# BalanceCar.net
KiCad netlist of a schematic drawn in Altium Designer
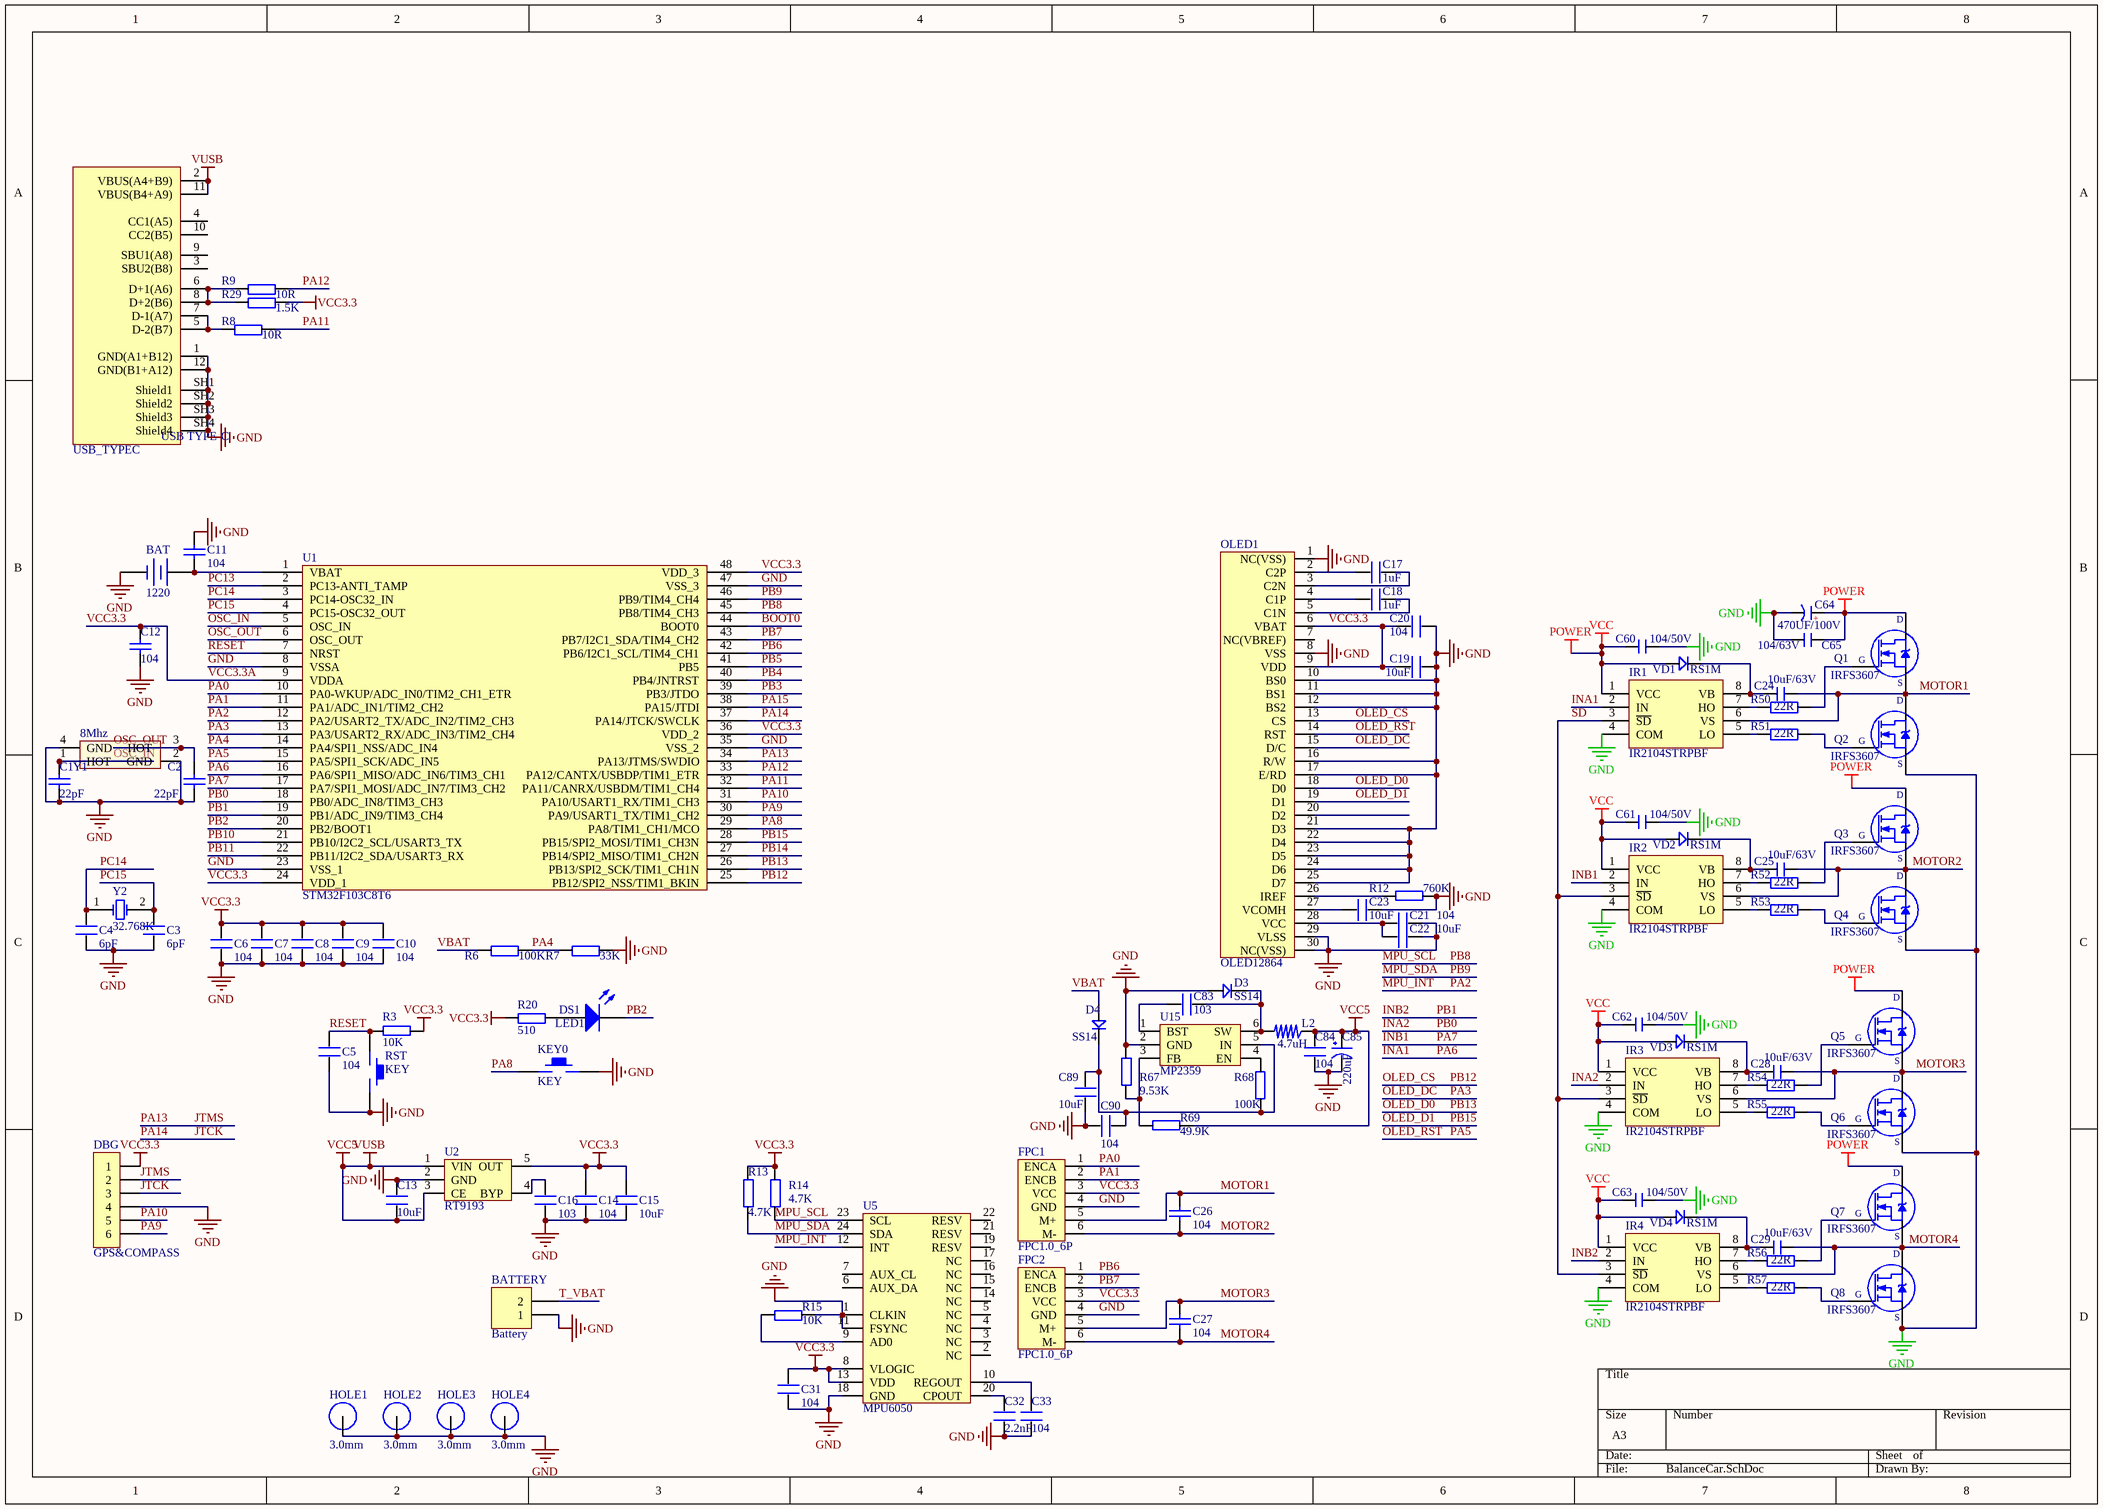
[diagram p0: BalanceCar.SchDoc]

(export (version "E")
  (design (tool "Eeschema 10.0.6"))
  (components
    (comp (ref "BAT")
      (value "1220")
      (footprint "CR1220_B")
      (description "微型电池")
      (fields (field (name "版权归属") "源创客"))
      (libsource (lib "IMX6UL_ALPHA(底板)_V2.0") (part "CR-3V"))
    )
    (comp (ref "BATTERY")
      (value "Battery")
      (footprint "HDR2.54-LI-2P")
      (description "Header, 2-Pin")
      (fields (field (name "PUBLISHER") "Altium Limited"))
      (libsource (lib "WarShip V3 STM32103封装库") (part "Header 2"))
    )
    (comp (ref "C1") (value "22pF") (footprint "C 0603_L") (libsource (lib "L476") (part "CAP")))
    (comp (ref "C2") (value "22pF") (footprint "C 0603_L") (libsource (lib "L476") (part "CAP")))
    (comp (ref "C3")
      (value "6pF")
      (footprint "C 0603_L")
      (libsource (lib "WarShip V3 STM32103封装库") (part "C"))
    )
    (comp (ref "C4")
      (value "6pF")
      (footprint "C 0603_L")
      (libsource (lib "WarShip V3 STM32103封装库") (part "C"))
    )
    (comp (ref "C5")
      (value "104")
      (footprint "C 0603_L")
      (libsource (lib "WarShip V3 STM32103封装库") (part "C"))
    )
    (comp (ref "C6")
      (value "104")
      (footprint "C 0603_L")
      (libsource (lib "WarShip V3 STM32103封装库") (part "C"))
    )
    (comp (ref "C7")
      (value "104")
      (footprint "C 0603_L")
      (libsource (lib "WarShip V3 STM32103封装库") (part "C"))
    )
    (comp (ref "C8")
      (value "104")
      (footprint "C 0603_L")
      (libsource (lib "WarShip V3 STM32103封装库") (part "C"))
    )
    (comp (ref "C9")
      (value "104")
      (footprint "C 0603_L")
      (libsource (lib "WarShip V3 STM32103封装库") (part "C"))
    )
    (comp (ref "C10")
      (value "104")
      (footprint "C 0603_L")
      (libsource (lib "WarShip V3 STM32103封装库") (part "C"))
    )
    (comp (ref "C11") (value "104") (footprint "C 0603_L") (libsource (lib "L476") (part "CAP")))
    (comp (ref "C12") (value "104") (footprint "C 0603_L") (libsource (lib "L476") (part "CAP")))
    (comp (ref "C13")
      (value "10uF")
      (footprint "C 0603_L")
      (libsource (lib "WarShip V3 STM32103封装库") (part "C"))
    )
    (comp (ref "C14")
      (value "104")
      (footprint "C 0603_L")
      (libsource (lib "WarShip V3 STM32103封装库") (part "C"))
    )
    (comp (ref "C15")
      (value "10uF")
      (footprint "C 0603_L")
      (libsource (lib "WarShip V3 STM32103封装库") (part "C"))
    )
    (comp (ref "C16")
      (value "103")
      (footprint "C 0603_L")
      (libsource (lib "WarShip V3 STM32103封装库") (part "C"))
    )
    (comp (ref "C17")
      (value "1uF")
      (footprint "C 0603_L")
      (libsource (lib "WarShip V3 STM32103封装库") (part "C"))
    )
    (comp (ref "C18")
      (value "1uF")
      (footprint "C 0603_L")
      (libsource (lib "WarShip V3 STM32103封装库") (part "C"))
    )
    (comp (ref "C19")
      (value "10uF")
      (footprint "C 0603_L")
      (libsource (lib "WarShip V3 STM32103封装库") (part "C"))
    )
    (comp (ref "C20")
      (value "104")
      (footprint "C 0603_L")
      (libsource (lib "WarShip V3 STM32103封装库") (part "C"))
    )
    (comp (ref "C21")
      (value "10uF")
      (footprint "C 0603_L")
      (libsource (lib "WarShip V3 STM32103封装库") (part "C"))
    )
    (comp (ref "C22")
      (value "104")
      (footprint "C 0603_L")
      (libsource (lib "WarShip V3 STM32103封装库") (part "C"))
    )
    (comp (ref "C23")
      (value "10uF")
      (footprint "C 0603_L")
      (libsource (lib "WarShip V3 STM32103封装库") (part "C"))
    )
    (comp (ref "C24")
      (value "10uF/63V")
      (footprint "C 0603_L")
      (description "无极性贴片电容")
      (fields (field (name "版权归属") "源创客"))
      (libsource (lib "电阻-电容-电感") (part "C"))
    )
    (comp (ref "C25")
      (value "10uF/63V")
      (footprint "C 0603_L")
      (description "无极性贴片电容")
      (fields (field (name "版权归属") "源创客"))
      (libsource (lib "电阻-电容-电感") (part "C"))
    )
    (comp (ref "C26") (value "104") (footprint "C 0603_L") (libsource (lib "L476") (part "CAP")))
    (comp (ref "C27") (value "104") (footprint "C 0603_L") (libsource (lib "L476") (part "CAP")))
    (comp (ref "C28")
      (value "10uF/63V")
      (footprint "C 0603_L")
      (description "无极性贴片电容")
      (fields (field (name "版权归属") "源创客"))
      (libsource (lib "电阻-电容-电感") (part "C"))
    )
    (comp (ref "C29")
      (value "10uF/63V")
      (footprint "C 0603_L")
      (description "无极性贴片电容")
      (fields (field (name "版权归属") "源创客"))
      (libsource (lib "电阻-电容-电感") (part "C"))
    )
    (comp (ref "C31")
      (value "104")
      (footprint "C 0603_L")
      (libsource (lib "WarShip V3 STM32103封装库") (part "C"))
    )
    (comp (ref "C32")
      (value "2.2nF")
      (footprint "C 0603_L")
      (libsource (lib "WarShip V3 STM32103封装库") (part "C"))
    )
    (comp (ref "C33")
      (value "104")
      (footprint "C 0603_L")
      (libsource (lib "WarShip V3 STM32103封装库") (part "C"))
    )
    (comp (ref "C60")
      (value "104/50V")
      (footprint "C 0603_L")
      (description "无极性贴片电容")
      (fields (field (name "版权归属") "源创客"))
      (libsource (lib "电阻-电容-电感") (part "C"))
    )
    (comp (ref "C61")
      (value "104/50V")
      (footprint "C 0603_L")
      (description "无极性贴片电容")
      (fields (field (name "版权归属") "源创客"))
      (libsource (lib "电阻-电容-电感") (part "C"))
    )
    (comp (ref "C62")
      (value "104/50V")
      (footprint "C 0603_L")
      (description "无极性贴片电容")
      (fields (field (name "版权归属") "源创客"))
      (libsource (lib "电阻-电容-电感") (part "C"))
    )
    (comp (ref "C63")
      (value "104/50V")
      (footprint "C 0603_L")
      (description "无极性贴片电容")
      (fields (field (name "版权归属") "源创客"))
      (libsource (lib "电阻-电容-电感") (part "C"))
    )
    (comp (ref "C64")
      (value "470UF/100V")
      (footprint "CAP 5.0*10*20 - BK")
      (description "直插电解电容")
      (fields (field (name "版权归属") "源创客"))
      (libsource (lib "电阻-电容-电感") (part "C-CAP"))
    )
    (comp (ref "C65")
      (value "104/63V")
      (footprint "C 1206_L")
      (description "无极性贴片电容")
      (fields (field (name "版权归属") "源创客"))
      (libsource (lib "电阻-电容-电感") (part "C"))
    )
    (comp (ref "C83") (value "103") (footprint "C 0603_L") (libsource (lib "ALIENTEK_COMPONENT") (part "C")))
    (comp (ref "C84") (value "104") (footprint "C 0603_L") (libsource (lib "MYCOMLIB") (part "C")))
    (comp (ref "C85") (value "220uF") (footprint "CM D(6.3*5.4)") (libsource (lib "MYCOMLIB") (part "CAP")))
    (comp (ref "C89") (value "10uF") (footprint "C 0603_L") (libsource (lib "ALIENTEK_COMPONENT") (part "C")))
    (comp (ref "C90") (value "104") (footprint "C 0603_L") (libsource (lib "MYCOMLIB") (part "C")))
    (comp (ref "D3")
      (value "SS14")
      (footprint "SMA")
      (description "1N4148")
      (libsource (lib "MYCOMLIB") (part "D"))
    )
    (comp (ref "D4")
      (value "SS14")
      (footprint "SMA")
      (description "1N4148")
      (libsource (lib "MYCOMLIB") (part "D"))
    )
    (comp (ref "DBG")
      (value "GPS&COMPASS")
      (footprint "SH1.0 S-W-6P")
      (description "6P接插件")
      (fields (field (name "版权归属") "源创客"))
      (libsource (lib "ATKF405 V1.1") (part "Header 6"))
    )
    (comp (ref "DS1")
      (value "LED1")
      (footprint "LED 0603R")
      (description "Typical RED, GREEN, YELLOW, AMBER GaAs LED")
      (fields (field (name "PUBLISHER") "Altium Limited"))
      (libsource (lib "WarShip V3 STM32103封装库") (part "LED2"))
    )
    (comp (ref "FPC1")
      (value "FPC1.0_6P")
      (footprint "FPC_1.0_6P")
      (libsource (lib "MOTOR_FPC") (part "FPC"))
    )
    (comp (ref "FPC2")
      (value "FPC1.0_6P")
      (footprint "FPC_1.0_6P")
      (libsource (lib "MOTOR_FPC") (part "FPC"))
    )
    (comp (ref "HOLE1")
      (value "3.0mm")
      (footprint "HOLE-M3")
      (fields (field (name "Comment") "HOLE"))
      (libsource (lib "YS_BDC_V1") (part "HOLE"))
    )
    (comp (ref "HOLE2")
      (value "3.0mm")
      (footprint "HOLE-M3")
      (fields (field (name "Comment") "HOLE"))
      (libsource (lib "YS_BDC_V1") (part "HOLE"))
    )
    (comp (ref "HOLE3")
      (value "3.0mm")
      (footprint "HOLE-M3")
      (fields (field (name "Comment") "HOLE"))
      (libsource (lib "YS_BDC_V1") (part "HOLE"))
    )
    (comp (ref "HOLE4")
      (value "3.0mm")
      (footprint "HOLE-M3")
      (fields (field (name "Comment") "HOLE"))
      (libsource (lib "YS_BDC_V1") (part "HOLE"))
    )
    (comp (ref "IR1")
      (value "IR2104STRPBF")
      (footprint "SOP8_L")
      (description "HALF-BRIDGE DRIVER")
      (libsource (lib "YS_BDC_V1") (part "IR2104STRPBF"))
    )
    (comp (ref "IR2")
      (value "IR2104STRPBF")
      (footprint "SOP8_L")
      (description "HALF-BRIDGE DRIVER")
      (libsource (lib "YS_BDC_V1") (part "IR2104STRPBF"))
    )
    (comp (ref "IR3")
      (value "IR2104STRPBF")
      (footprint "SOP8_L")
      (description "HALF-BRIDGE DRIVER")
      (libsource (lib "YS_BDC_V1") (part "IR2104STRPBF"))
    )
    (comp (ref "IR4")
      (value "IR2104STRPBF")
      (footprint "SOP8_L")
      (description "HALF-BRIDGE DRIVER")
      (libsource (lib "YS_BDC_V1") (part "IR2104STRPBF"))
    )
    (comp (ref "KEY0")
      (value "KEY")
      (footprint "TSW DIP-6*6*9")
      (libsource (lib "STM32F429核心板封装库") (part "KEY_M"))
    )
    (comp (ref "L2")
      (value "4.7uH")
      (footprint "CDRH73")
      (libsource (lib "ALIENTEK_COMPONENT") (part "L_SOP"))
    )
    (comp (ref "OLED1") (value "OLED12864") (libsource (lib "OLED模块封装库") (part "OLED12864")))
    (comp (ref "Q1")
      (value "IRFS3607")
      (footprint "TO263-3B")
      (description "N-Channel Power MOSFET")
      (fields (field (name "PUBLISHER") "Altium Limited"))
      (libsource (lib "YS_BDC_V1") (part "NMOS-2"))
    )
    (comp (ref "Q2")
      (value "IRFS3607")
      (footprint "TO263-3B")
      (description "N-Channel Power MOSFET")
      (fields (field (name "PUBLISHER") "Altium Limited"))
      (libsource (lib "YS_BDC_V1") (part "NMOS-2"))
    )
    (comp (ref "Q3")
      (value "IRFS3607")
      (footprint "TO263-3B")
      (description "N-Channel Power MOSFET")
      (fields (field (name "PUBLISHER") "Altium Limited"))
      (libsource (lib "YS_BDC_V1") (part "NMOS-2"))
    )
    (comp (ref "Q4")
      (value "IRFS3607")
      (footprint "TO263-3B")
      (description "N-Channel Power MOSFET")
      (fields (field (name "PUBLISHER") "Altium Limited"))
      (libsource (lib "YS_BDC_V1") (part "NMOS-2"))
    )
    (comp (ref "Q5")
      (value "IRFS3607")
      (footprint "TO263-3B")
      (description "N-Channel Power MOSFET")
      (fields (field (name "PUBLISHER") "Altium Limited"))
      (libsource (lib "YS_BDC_V1") (part "NMOS-2"))
    )
    (comp (ref "Q6")
      (value "IRFS3607")
      (footprint "TO263-3B")
      (description "N-Channel Power MOSFET")
      (fields (field (name "PUBLISHER") "Altium Limited"))
      (libsource (lib "YS_BDC_V1") (part "NMOS-2"))
    )
    (comp (ref "Q7")
      (value "IRFS3607")
      (footprint "TO263-3B")
      (description "N-Channel Power MOSFET")
      (fields (field (name "PUBLISHER") "Altium Limited"))
      (libsource (lib "YS_BDC_V1") (part "NMOS-2"))
    )
    (comp (ref "Q8")
      (value "IRFS3607")
      (footprint "TO263-3B")
      (description "N-Channel Power MOSFET")
      (fields (field (name "PUBLISHER") "Altium Limited"))
      (libsource (lib "YS_BDC_V1") (part "NMOS-2"))
    )
    (comp (ref "R3")
      (value "10K")
      (footprint "R 0603_L")
      (libsource (lib "WarShip V3 STM32103封装库") (part "R"))
    )
    (comp (ref "R6")
      (value "100K")
      (footprint "R 0603_L")
      (libsource (lib "WarShip V3 STM32103封装库") (part "R"))
    )
    (comp (ref "R7")
      (value "33K")
      (footprint "R 0603_L")
      (libsource (lib "WarShip V3 STM32103封装库") (part "R"))
    )
    (comp (ref "R8")
      (value "10R")
      (footprint "R 0603_L")
      (libsource (lib "WarShip V3 STM32103封装库") (part "R"))
    )
    (comp (ref "R9")
      (value "10R")
      (footprint "R 0603_L")
      (libsource (lib "WarShip V3 STM32103封装库") (part "R"))
    )
    (comp (ref "R12")
      (value "760K")
      (footprint "R 0603_L")
      (libsource (lib "WarShip V3 STM32103封装库") (part "R"))
    )
    (comp (ref "R13")
      (value "4.7K")
      (footprint "R 0603_L")
      (libsource (lib "WarShip V3 STM32103封装库") (part "R"))
    )
    (comp (ref "R14")
      (value "4.7K")
      (footprint "R 0603_L")
      (libsource (lib "WarShip V3 STM32103封装库") (part "R"))
    )
    (comp (ref "R15")
      (value "10K")
      (footprint "R 0603_L")
      (libsource (lib "WarShip V3 STM32103封装库") (part "R"))
    )
    (comp (ref "R20")
      (value "510")
      (footprint "R 0603_L")
      (libsource (lib "WarShip V3 STM32103封装库") (part "R"))
    )
    (comp (ref "R29")
      (value "1.5K")
      (footprint "R 0603_L")
      (libsource (lib "WarShip V3 STM32103封装库") (part "R"))
    )
    (comp (ref "R50")
      (value "22R")
      (footprint "R 0603_L")
      (description "贴片电阻")
      (fields (field (name "版权归属") "源创客"))
      (libsource (lib "电阻-电容-电感") (part "R"))
    )
    (comp (ref "R51")
      (value "22R")
      (footprint "R 0603_L")
      (description "贴片电阻")
      (fields (field (name "版权归属") "源创客"))
      (libsource (lib "电阻-电容-电感") (part "R"))
    )
    (comp (ref "R52")
      (value "22R")
      (footprint "R 0603_L")
      (description "贴片电阻")
      (fields (field (name "版权归属") "源创客"))
      (libsource (lib "电阻-电容-电感") (part "R"))
    )
    (comp (ref "R53")
      (value "22R")
      (footprint "R 0603_L")
      (description "贴片电阻")
      (fields (field (name "版权归属") "源创客"))
      (libsource (lib "电阻-电容-电感") (part "R"))
    )
    (comp (ref "R54")
      (value "22R")
      (footprint "R 0603_L")
      (description "贴片电阻")
      (fields (field (name "版权归属") "源创客"))
      (libsource (lib "电阻-电容-电感") (part "R"))
    )
    (comp (ref "R55")
      (value "22R")
      (footprint "R 0603_L")
      (description "贴片电阻")
      (fields (field (name "版权归属") "源创客"))
      (libsource (lib "电阻-电容-电感") (part "R"))
    )
    (comp (ref "R56")
      (value "22R")
      (footprint "R 0603_L")
      (description "贴片电阻")
      (fields (field (name "版权归属") "源创客"))
      (libsource (lib "电阻-电容-电感") (part "R"))
    )
    (comp (ref "R57")
      (value "22R")
      (footprint "R 0603_L")
      (description "贴片电阻")
      (fields (field (name "版权归属") "源创客"))
      (libsource (lib "电阻-电容-电感") (part "R"))
    )
    (comp (ref "R67")
      (value "9.53K")
      (footprint "R 0603_L")
      (libsource (lib "ALIENTEK_COMPONENT") (part "R"))
    )
    (comp (ref "R68") (value "100K") (footprint "R 0603_L") (libsource (lib "ALIENTEK_COMPONENT") (part "R")))
    (comp (ref "R69")
      (value "49.9K")
      (footprint "R 0603_L")
      (libsource (lib "ALIENTEK_COMPONENT") (part "R"))
    )
    (comp (ref "RST") (value "KEY") (footprint "TSW DIP-6*6*9") (libsource (lib "") (part "KEY_M_1")))
    (comp (ref "U1")
      (value "STM32F103C8T6")
      (footprint "LQFP-48PIN")
      (libsource (lib "Pandora_STM32L4_Board_V2.4") (part "U-STM32F103C8T6"))
    )
    (comp (ref "U2")
      (value "RT9193")
      (footprint "SOT23-5L")
      (description "3.3V 500mA LDO")
      (libsource (lib "STM32H743核心板封装库") (part "CAT6219-330TD"))
    )
    (comp (ref "U5")
      (value "MPU6050")
      (footprint "QFN24 4x4_N")
      (description "9轴运动处理传感器")
      (libsource (lib "ATK-MPU6050六轴传感器模块") (part "MPU6050"))
    )
    (comp (ref "U15")
      (value "MP2359")
      (footprint "SOT23-6L")
      (description "DC DC Step Down IC")
      (libsource (lib "ALIENTEK_COMPONENT") (part "MP2359"))
    )
    (comp (ref "USB_TYPEC")
      (value "USB TypeC")
      (footprint "USB Type-C")
      (description "12P TypeC 母座")
      (libsource (lib "ESP32_Weather") (part "USB Type-C"))
    )
    (comp (ref "VD1")
      (value "RS1M")
      (footprint "SOD-123F")
      (description "肖特基二极管")
      (fields (field (name "版权归属") "源创客"))
      (libsource (lib "二极管-整流桥") (part "SS14"))
    )
    (comp (ref "VD2")
      (value "RS1M")
      (footprint "SOD-123F")
      (description "肖特基二极管")
      (fields (field (name "版权归属") "源创客"))
      (libsource (lib "二极管-整流桥") (part "SS14"))
    )
    (comp (ref "VD3")
      (value "RS1M")
      (footprint "SOD-123F")
      (description "肖特基二极管")
      (fields (field (name "版权归属") "源创客"))
      (libsource (lib "二极管-整流桥") (part "SS14"))
    )
    (comp (ref "VD4")
      (value "RS1M")
      (footprint "SOD-123F")
      (description "肖特基二极管")
      (fields (field (name "版权归属") "源创客"))
      (libsource (lib "二极管-整流桥") (part "SS14"))
    )
    (comp (ref "Y1")
      (value "8Mhz")
      (footprint "XTAL-3225")
      (description "3225贴片无源晶振")
      (libsource (lib "ALIENTEK_COMPONENT") (part "XTAL_3225"))
    )
    (comp (ref "Y2")
      (value "32.768K")
      (footprint "OSC 3215-2P")
      (description "Crystal Oscillator")
      (fields (field (name "PUBLISHER") "Altium Limited"))
      (libsource (lib "WarShip V3 STM32103封装库") (part "XTAL"))
    )
  )
  (nets
    (net (code "1") (name "/BOOT0") (class "Default")
      (node (ref "U1") (pin "44") (pinfunction "BOOT0_44") (pintype "passive"))
    )
    (net (code "2") (name "/INA1") (class "Default")
      (node (ref "IR1") (pin "2") (pinfunction "IN_2") (pintype "passive"))
      (node (ref "U1") (pin "16") (pinfunction "PA6/SPI1_MISO/ADC_IN6/TIM3_CH1_16") (pintype "passive"))
    )
    (net (code "3") (name "/INA2") (class "Default")
      (node (ref "IR3") (pin "2") (pinfunction "IN_2") (pintype "passive"))
      (node (ref "U1") (pin "18") (pinfunction "PB0/ADC_IN8/TIM3_CH3_18") (pintype "passive"))
    )
    (net (code "4") (name "/INB1") (class "Default")
      (node (ref "IR2") (pin "2") (pinfunction "IN_2") (pintype "passive"))
      (node (ref "U1") (pin "17") (pinfunction "PA7/SPI1_MOSI/ADC_IN7/TIM3_CH2_17") (pintype "passive"))
    )
    (net (code "5") (name "/INB2") (class "Default")
      (node (ref "IR4") (pin "2") (pinfunction "IN_2") (pintype "passive"))
      (node (ref "U1") (pin "19") (pinfunction "PB1/ADC_IN9/TIM3_CH4_19") (pintype "passive"))
    )
    (net (code "6") (name "/JTCK") (class "Default")
      (node (ref "DBG") (pin "3") (pinfunction "3_3") (pintype "passive"))
      (node (ref "U1") (pin "37") (pinfunction "PA14/JTCK/SWCLK_37") (pintype "passive"))
    )
    (net (code "7") (name "/JTMS") (class "Default")
      (node (ref "DBG") (pin "2") (pinfunction "2_2") (pintype "passive"))
      (node (ref "U1") (pin "34") (pinfunction "PA13/JTMS/SWDIO_34") (pintype "passive"))
    )
    (net (code "8") (name "/MOTOR1") (class "Default")
      (node (ref "C24") (pin "1") (pinfunction "1_1") (pintype "passive"))
      (node (ref "C26") (pin "2") (pinfunction "2_2") (pintype "passive"))
      (node (ref "FPC1") (pin "5") (pinfunction "M+_5") (pintype "passive"))
      (node (ref "IR1") (pin "6") (pinfunction "VS_6") (pintype "passive"))
      (node (ref "Q1") (pin "3") (pinfunction "S_3") (pintype "passive"))
      (node (ref "Q2") (pin "2") (pinfunction "D_2") (pintype "passive"))
    )
    (net (code "9") (name "/MOTOR2") (class "Default")
      (node (ref "C25") (pin "1") (pinfunction "1_1") (pintype "passive"))
      (node (ref "C26") (pin "1") (pinfunction "1_1") (pintype "passive"))
      (node (ref "FPC1") (pin "6") (pinfunction "M-_6") (pintype "passive"))
      (node (ref "IR2") (pin "6") (pinfunction "VS_6") (pintype "passive"))
      (node (ref "Q3") (pin "3") (pinfunction "S_3") (pintype "passive"))
      (node (ref "Q4") (pin "2") (pinfunction "D_2") (pintype "passive"))
    )
    (net (code "10") (name "/MOTOR3") (class "Default")
      (node (ref "C27") (pin "2") (pinfunction "2_2") (pintype "passive"))
      (node (ref "C28") (pin "1") (pinfunction "1_1") (pintype "passive"))
      (node (ref "FPC2") (pin "5") (pinfunction "M+_5") (pintype "passive"))
      (node (ref "IR3") (pin "6") (pinfunction "VS_6") (pintype "passive"))
      (node (ref "Q5") (pin "3") (pinfunction "S_3") (pintype "passive"))
      (node (ref "Q6") (pin "2") (pinfunction "D_2") (pintype "passive"))
    )
    (net (code "11") (name "/MOTOR4") (class "Default")
      (node (ref "C27") (pin "1") (pinfunction "1_1") (pintype "passive"))
      (node (ref "C29") (pin "1") (pinfunction "1_1") (pintype "passive"))
      (node (ref "FPC2") (pin "6") (pinfunction "M-_6") (pintype "passive"))
      (node (ref "IR4") (pin "6") (pinfunction "VS_6") (pintype "passive"))
      (node (ref "Q7") (pin "3") (pinfunction "S_3") (pintype "passive"))
      (node (ref "Q8") (pin "2") (pinfunction "D_2") (pintype "passive"))
    )
    (net (code "12") (name "/MPU_INT") (class "Default")
      (node (ref "U1") (pin "12") (pinfunction "PA2/USART2_TX/ADC_IN2/TIM2_CH3_12") (pintype "passive"))
      (node (ref "U5") (pin "12") (pinfunction "INT_12") (pintype "passive"))
    )
    (net (code "13") (name "/MPU_SCL") (class "Default")
      (node (ref "R14") (pin "1") (pintype "passive"))
      (node (ref "U1") (pin "45") (pinfunction "PB8/TIM4_CH3_45") (pintype "passive"))
      (node (ref "U5") (pin "23") (pinfunction "SCL_23") (pintype "passive"))
    )
    (net (code "14") (name "/MPU_SDA") (class "Default")
      (node (ref "R13") (pin "1") (pintype "passive"))
      (node (ref "U1") (pin "46") (pinfunction "PB9/TIM4_CH4_46") (pintype "passive"))
      (node (ref "U5") (pin "24") (pinfunction "SDA_24") (pintype "passive"))
    )
    (net (code "15") (name "/OLED_CS") (class "Default")
      (node (ref "OLED1") (pin "13") (pinfunction "CS_13") (pintype "passive"))
      (node (ref "U1") (pin "25") (pinfunction "PB12/SPI2_NSS/TIM1_BKIN_25") (pintype "passive"))
    )
    (net (code "16") (name "/OLED_D0") (class "Default")
      (node (ref "OLED1") (pin "18") (pinfunction "D0_18") (pintype "passive"))
      (node (ref "U1") (pin "26") (pinfunction "PB13/SPI2_SCK/TIM1_CH1N_26") (pintype "passive"))
    )
    (net (code "17") (name "/OLED_D1") (class "Default")
      (node (ref "OLED1") (pin "19") (pinfunction "D1_19") (pintype "passive"))
      (node (ref "U1") (pin "28") (pinfunction "PB15/SPI2_MOSI/TIM1_CH3N_28") (pintype "passive"))
    )
    (net (code "18") (name "/OLED_DC") (class "Default")
      (node (ref "OLED1") (pin "15") (pinfunction "D/C_15") (pintype "passive"))
      (node (ref "U1") (pin "13") (pinfunction "PA3/USART2_RX/ADC_IN3/TIM2_CH4_13") (pintype "passive"))
    )
    (net (code "19") (name "/OLED_RST") (class "Default")
      (node (ref "OLED1") (pin "14") (pinfunction "RST_14") (pintype "passive"))
      (node (ref "U1") (pin "15") (pinfunction "PA5/SPI1_SCK/ADC_IN5_15") (pintype "passive"))
    )
    (net (code "20") (name "/OSC_IN") (class "Default")
      (node (ref "C1") (pin "2") (pinfunction "2_2") (pintype "passive"))
      (node (ref "U1") (pin "5") (pinfunction "OSC_IN_5") (pintype "passive"))
      (node (ref "Y1") (pin "1") (pinfunction "HOT_1") (pintype "passive"))
    )
    (net (code "21") (name "/OSC_OUT") (class "Default")
      (node (ref "C2") (pin "2") (pinfunction "2_2") (pintype "passive"))
      (node (ref "U1") (pin "6") (pinfunction "OSC_OUT_6") (pintype "passive"))
      (node (ref "Y1") (pin "3") (pinfunction "HOT_3") (pintype "passive"))
    )
    (net (code "22") (name "/PA0") (class "Default")
      (node (ref "FPC1") (pin "1") (pinfunction "ENCA_1") (pintype "passive"))
      (node (ref "U1") (pin "10") (pinfunction "PA0-WKUP/ADC_IN0/TIM2_CH1_ETR_10") (pintype "passive"))
    )
    (net (code "23") (name "/PA1") (class "Default")
      (node (ref "FPC1") (pin "2") (pinfunction "ENCB_2") (pintype "passive"))
      (node (ref "U1") (pin "11") (pinfunction "PA1/ADC_IN1/TIM2_CH2_11") (pintype "passive"))
    )
    (net (code "24") (name "/PA4") (class "Default")
      (node (ref "R6") (pin "2") (pintype "passive"))
      (node (ref "R7") (pin "1") (pintype "passive"))
      (node (ref "U1") (pin "14") (pinfunction "PA4/SPI1_NSS/ADC_IN4_14") (pintype "passive"))
    )
    (net (code "25") (name "/PA8") (class "Default")
      (node (ref "KEY0") (pin "1") (pinfunction "1_1") (pintype "passive"))
      (node (ref "U1") (pin "29") (pinfunction "PA8/TIM1_CH1/MCO_29") (pintype "passive"))
    )
    (net (code "26") (name "/PA9") (class "Default")
      (node (ref "DBG") (pin "6") (pinfunction "6_6") (pintype "passive"))
      (node (ref "U1") (pin "30") (pinfunction "PA9/USART1_TX/TIM1_CH2_30") (pintype "passive"))
    )
    (net (code "27") (name "/PA10") (class "Default")
      (node (ref "DBG") (pin "5") (pinfunction "5_5") (pintype "passive"))
      (node (ref "U1") (pin "31") (pinfunction "PA10/USART1_RX/TIM1_CH3_31") (pintype "passive"))
    )
    (net (code "28") (name "/PA11") (class "Default")
      (node (ref "R8") (pin "2") (pintype "passive"))
      (node (ref "U1") (pin "32") (pinfunction "PA11/CANRX/USBDM/TIM1_CH4_32") (pintype "passive"))
    )
    (net (code "29") (name "/PA12") (class "Default")
      (node (ref "R9") (pin "2") (pintype "passive"))
      (node (ref "U1") (pin "33") (pinfunction "PA12/CANTX/USBDP/TIM1_ETR_33") (pintype "passive"))
    )
    (net (code "30") (name "/PA15") (class "Default")
      (node (ref "U1") (pin "38") (pinfunction "PA15/JTDI_38") (pintype "passive"))
    )
    (net (code "31") (name "/PB2") (class "Default")
      (node (ref "DS1") (pin "2") (pinfunction "K_2") (pintype "passive"))
      (node (ref "U1") (pin "20") (pinfunction "PB2/BOOT1_20") (pintype "passive"))
    )
    (net (code "32") (name "/PB3") (class "Default")
      (node (ref "U1") (pin "39") (pinfunction "PB3/JTDO_39") (pintype "passive"))
    )
    (net (code "33") (name "/PB4") (class "Default")
      (node (ref "U1") (pin "40") (pinfunction "PB4/JNTRST_40") (pintype "passive"))
    )
    (net (code "34") (name "/PB5") (class "Default")
      (node (ref "U1") (pin "41") (pinfunction "PB5_41") (pintype "passive"))
    )
    (net (code "35") (name "/PB6") (class "Default")
      (node (ref "FPC2") (pin "1") (pinfunction "ENCA_1") (pintype "passive"))
      (node (ref "U1") (pin "42") (pinfunction "PB6/I2C1_SCL/TIM4_CH1_42") (pintype "passive"))
    )
    (net (code "36") (name "/PB7") (class "Default")
      (node (ref "FPC2") (pin "2") (pinfunction "ENCB_2") (pintype "passive"))
      (node (ref "U1") (pin "43") (pinfunction "PB7/I2C1_SDA/TIM4_CH2_43") (pintype "passive"))
    )
    (net (code "37") (name "/PB10") (class "Default")
      (node (ref "U1") (pin "21") (pinfunction "PB10/I2C2_SCL/USART3_TX_21") (pintype "passive"))
    )
    (net (code "38") (name "/PB11") (class "Default")
      (node (ref "U1") (pin "22") (pinfunction "PB11/I2C2_SDA/USART3_RX_22") (pintype "passive"))
    )
    (net (code "39") (name "/PB14") (class "Default")
      (node (ref "U1") (pin "27") (pinfunction "PB14/SPI2_MISO/TIM1_CH2N_27") (pintype "passive"))
    )
    (net (code "40") (name "/PC13") (class "Default")
      (node (ref "U1") (pin "2") (pinfunction "PC13-ANTI_TAMP_2") (pintype "passive"))
    )
    (net (code "41") (name "/PC14") (class "Default")
      (node (ref "C4") (pin "2") (pintype "passive"))
      (node (ref "U1") (pin "3") (pinfunction "PC14-OSC32_IN_3") (pintype "passive"))
      (node (ref "Y2") (pin "1") (pinfunction "OSC1_1") (pintype "passive"))
    )
    (net (code "42") (name "/PC15") (class "Default")
      (node (ref "C3") (pin "2") (pintype "passive"))
      (node (ref "U1") (pin "4") (pinfunction "PC15-OSC32_OUT_4") (pintype "passive"))
      (node (ref "Y2") (pin "2") (pinfunction "OSC2_2") (pintype "passive"))
    )
    (net (code "43") (name "/RESET") (class "Default")
      (node (ref "C5") (pin "2") (pintype "passive"))
      (node (ref "R3") (pin "2") (pintype "passive"))
      (node (ref "RST") (pin "1") (pinfunction "1_1") (pintype "passive"))
      (node (ref "U1") (pin "7") (pinfunction "NRST_7") (pintype "passive"))
    )
    (net (code "44") (name "/SD") (class "Default")
      (node (ref "IR1") (pin "3") (pinfunction "~{SD}_3") (pintype "passive"))
      (node (ref "IR2") (pin "3") (pinfunction "~{SD}_3") (pintype "passive"))
      (node (ref "IR3") (pin "3") (pinfunction "~{SD}_3") (pintype "passive"))
      (node (ref "IR4") (pin "3") (pinfunction "~{SD}_3") (pintype "passive"))
    )
    (net (code "45") (name "/T_VBAT") (class "Default")
      (node (ref "BATTERY") (pin "2") (pinfunction "2_2") (pintype "passive"))
    )
    (net (code "46") (name "/VBAT") (class "Default")
      (node (ref "D4") (pin "1") (pintype "passive"))
      (node (ref "R6") (pin "1") (pintype "passive"))
    )
    (net (code "47") (name "GND") (class "Default")
      (node (ref "BAT") (pin "2") (pinfunction "DC-_2") (pintype "passive"))
      (node (ref "BATTERY") (pin "1") (pinfunction "1_1") (pintype "passive"))
      (node (ref "C1") (pin "1") (pinfunction "1_1") (pintype "passive"))
      (node (ref "C10") (pin "1") (pintype "passive"))
      (node (ref "C11") (pin "2") (pinfunction "2_2") (pintype "passive"))
      (node (ref "C12") (pin "1") (pinfunction "1_1") (pintype "passive"))
      (node (ref "C13") (pin "2") (pintype "passive"))
      (node (ref "C14") (pin "1") (pintype "passive"))
      (node (ref "C15") (pin "1") (pintype "passive"))
      (node (ref "C16") (pin "1") (pintype "passive"))
      (node (ref "C19") (pin "1") (pintype "passive"))
      (node (ref "C2") (pin "1") (pinfunction "1_1") (pintype "passive"))
      (node (ref "C20") (pin "1") (pintype "passive"))
      (node (ref "C21") (pin "1") (pintype "passive"))
      (node (ref "C22") (pin "1") (pintype "passive"))
      (node (ref "C23") (pin "1") (pintype "passive"))
      (node (ref "C3") (pin "1") (pintype "passive"))
      (node (ref "C31") (pin "1") (pintype "passive"))
      (node (ref "C32") (pin "1") (pintype "passive"))
      (node (ref "C33") (pin "1") (pintype "passive"))
      (node (ref "C4") (pin "1") (pintype "passive"))
      (node (ref "C5") (pin "1") (pintype "passive"))
      (node (ref "C6") (pin "1") (pintype "passive"))
      (node (ref "C60") (pin "1") (pinfunction "1_1") (pintype "passive"))
      (node (ref "C61") (pin "1") (pinfunction "1_1") (pintype "passive"))
      (node (ref "C62") (pin "1") (pinfunction "1_1") (pintype "passive"))
      (node (ref "C63") (pin "1") (pinfunction "1_1") (pintype "passive"))
      (node (ref "C64") (pin "2") (pinfunction "K_2") (pintype "passive"))
      (node (ref "C65") (pin "2") (pinfunction "2_2") (pintype "passive"))
      (node (ref "C7") (pin "1") (pintype "passive"))
      (node (ref "C8") (pin "1") (pintype "passive"))
      (node (ref "C84") (pin "1") (pintype "passive"))
      (node (ref "C85") (pin "2") (pinfunction "GND_2") (pintype "passive"))
      (node (ref "C89") (pin "1") (pintype "passive"))
      (node (ref "C9") (pin "1") (pintype "passive"))
      (node (ref "C90") (pin "1") (pintype "passive"))
      (node (ref "D3") (pin "1") (pintype "passive"))
      (node (ref "DBG") (pin "4") (pinfunction "4_4") (pintype "passive"))
      (node (ref "FPC1") (pin "4") (pinfunction "GND_4") (pintype "passive"))
      (node (ref "FPC2") (pin "4") (pinfunction "GND_4") (pintype "passive"))
      (node (ref "HOLE1") (pin "1") (pintype "passive"))
      (node (ref "HOLE2") (pin "1") (pintype "passive"))
      (node (ref "HOLE3") (pin "1") (pintype "passive"))
      (node (ref "HOLE4") (pin "1") (pintype "passive"))
      (node (ref "IR1") (pin "4") (pinfunction "COM_4") (pintype "passive"))
      (node (ref "IR2") (pin "4") (pinfunction "COM_4") (pintype "passive"))
      (node (ref "IR3") (pin "4") (pinfunction "COM_4") (pintype "passive"))
      (node (ref "IR4") (pin "4") (pinfunction "COM_4") (pintype "passive"))
      (node (ref "KEY0") (pin "2") (pinfunction "2_2") (pintype "passive"))
      (node (ref "OLED1") (pin "1") (pinfunction "NC(VSS)_1") (pintype "passive"))
      (node (ref "OLED1") (pin "10") (pinfunction "BS0_10") (pintype "passive"))
      (node (ref "OLED1") (pin "11") (pinfunction "BS1_11") (pintype "passive"))
      (node (ref "OLED1") (pin "12") (pinfunction "BS2_12") (pintype "passive"))
      (node (ref "OLED1") (pin "16") (pinfunction "R/W_16") (pintype "passive"))
      (node (ref "OLED1") (pin "17") (pinfunction "E/RD_17") (pintype "passive"))
      (node (ref "OLED1") (pin "21") (pinfunction "D3_21") (pintype "passive"))
      (node (ref "OLED1") (pin "22") (pinfunction "D4_22") (pintype "passive"))
      (node (ref "OLED1") (pin "23") (pinfunction "D5_23") (pintype "passive"))
      (node (ref "OLED1") (pin "24") (pinfunction "D6_24") (pintype "passive"))
      (node (ref "OLED1") (pin "25") (pinfunction "D7_25") (pintype "passive"))
      (node (ref "OLED1") (pin "29") (pinfunction "VLSS_29") (pintype "passive"))
      (node (ref "OLED1") (pin "30") (pinfunction "NC(VSS)_30") (pintype "passive"))
      (node (ref "OLED1") (pin "8") (pinfunction "VSS_8") (pintype "passive"))
      (node (ref "Q2") (pin "3") (pinfunction "S_3") (pintype "passive"))
      (node (ref "Q4") (pin "3") (pinfunction "S_3") (pintype "passive"))
      (node (ref "Q6") (pin "3") (pinfunction "S_3") (pintype "passive"))
      (node (ref "Q8") (pin "3") (pinfunction "S_3") (pintype "passive"))
      (node (ref "R12") (pin "1") (pintype "passive"))
      (node (ref "R15") (pin "2") (pintype "passive"))
      (node (ref "R67") (pin "2") (pintype "passive"))
      (node (ref "R7") (pin "2") (pintype "passive"))
      (node (ref "RST") (pin "2") (pinfunction "2_2") (pintype "passive"))
      (node (ref "U1") (pin "23") (pinfunction "VSS_1_23") (pintype "passive"))
      (node (ref "U1") (pin "35") (pinfunction "VSS_2_35") (pintype "passive"))
      (node (ref "U1") (pin "47") (pinfunction "VSS_3_47") (pintype "passive"))
      (node (ref "U1") (pin "8") (pinfunction "VSSA_8") (pintype "passive"))
      (node (ref "U15") (pin "2") (pinfunction "GND_2") (pintype "passive"))
      (node (ref "U2") (pin "2") (pinfunction "GND_2") (pintype "passive"))
      (node (ref "U5") (pin "1") (pinfunction "CLKIN_1") (pintype "passive"))
      (node (ref "U5") (pin "11") (pinfunction "FSYNC_11") (pintype "passive"))
      (node (ref "U5") (pin "18") (pinfunction "GND_18") (pintype "passive"))
      (node (ref "USB_TYPEC") (pin "1") (pinfunction "GND(A1+B12)_1") (pintype "passive"))
      (node (ref "USB_TYPEC") (pin "12") (pinfunction "GND(B1+A12)_12") (pintype "passive"))
      (node (ref "USB_TYPEC") (pin "SH1") (pinfunction "Shield1_SH1") (pintype "passive"))
      (node (ref "USB_TYPEC") (pin "SH2") (pinfunction "Shield2_SH2") (pintype "passive"))
      (node (ref "USB_TYPEC") (pin "SH3") (pinfunction "Shield3_SH3") (pintype "passive"))
      (node (ref "USB_TYPEC") (pin "SH4") (pinfunction "Shield4_SH4") (pintype "passive"))
      (node (ref "Y1") (pin "2") (pinfunction "GND_2") (pintype "passive"))
      (node (ref "Y1") (pin "4") (pinfunction "GND_4") (pintype "passive"))
    )
    (net (code "48") (name "Net-(BAT-DC+)") (class "Default")
      (node (ref "BAT") (pin "1") (pinfunction "DC+_1") (pintype "passive"))
      (node (ref "C11") (pin "1") (pinfunction "1_1") (pintype "passive"))
      (node (ref "U1") (pin "1") (pinfunction "VBAT_1") (pintype "passive"))
    )
    (net (code "49") (name "Net-(DS1-A)") (class "Default")
      (node (ref "DS1") (pin "1") (pinfunction "A_1") (pintype "passive"))
      (node (ref "R20") (pin "2") (pintype "passive"))
    )
    (net (code "50") (name "Net-(IR1-HO)") (class "Default")
      (node (ref "IR1") (pin "7") (pinfunction "HO_7") (pintype "passive"))
      (node (ref "R50") (pin "2") (pinfunction "2_2") (pintype "passive"))
    )
    (net (code "51") (name "Net-(IR1-LO)") (class "Default")
      (node (ref "IR1") (pin "5") (pinfunction "LO_5") (pintype "passive"))
      (node (ref "R51") (pin "2") (pinfunction "2_2") (pintype "passive"))
    )
    (net (code "52") (name "Net-(IR1-VB)") (class "Default")
      (node (ref "C24") (pin "2") (pinfunction "2_2") (pintype "passive"))
      (node (ref "IR1") (pin "8") (pinfunction "VB_8") (pintype "passive"))
      (node (ref "VD1") (pin "2") (pinfunction "K_2") (pintype "passive"))
    )
    (net (code "53") (name "Net-(IR2-HO)") (class "Default")
      (node (ref "IR2") (pin "7") (pinfunction "HO_7") (pintype "passive"))
      (node (ref "R52") (pin "2") (pinfunction "2_2") (pintype "passive"))
    )
    (net (code "54") (name "Net-(IR2-LO)") (class "Default")
      (node (ref "IR2") (pin "5") (pinfunction "LO_5") (pintype "passive"))
      (node (ref "R53") (pin "2") (pinfunction "2_2") (pintype "passive"))
    )
    (net (code "55") (name "Net-(IR2-VB)") (class "Default")
      (node (ref "C25") (pin "2") (pinfunction "2_2") (pintype "passive"))
      (node (ref "IR2") (pin "8") (pinfunction "VB_8") (pintype "passive"))
      (node (ref "VD2") (pin "2") (pinfunction "K_2") (pintype "passive"))
    )
    (net (code "56") (name "Net-(IR3-HO)") (class "Default")
      (node (ref "IR3") (pin "7") (pinfunction "HO_7") (pintype "passive"))
      (node (ref "R54") (pin "2") (pinfunction "2_2") (pintype "passive"))
    )
    (net (code "57") (name "Net-(IR3-LO)") (class "Default")
      (node (ref "IR3") (pin "5") (pinfunction "LO_5") (pintype "passive"))
      (node (ref "R55") (pin "2") (pinfunction "2_2") (pintype "passive"))
    )
    (net (code "58") (name "Net-(IR3-VB)") (class "Default")
      (node (ref "C28") (pin "2") (pinfunction "2_2") (pintype "passive"))
      (node (ref "IR3") (pin "8") (pinfunction "VB_8") (pintype "passive"))
      (node (ref "VD3") (pin "2") (pinfunction "K_2") (pintype "passive"))
    )
    (net (code "59") (name "Net-(IR4-HO)") (class "Default")
      (node (ref "IR4") (pin "7") (pinfunction "HO_7") (pintype "passive"))
      (node (ref "R56") (pin "2") (pinfunction "2_2") (pintype "passive"))
    )
    (net (code "60") (name "Net-(IR4-LO)") (class "Default")
      (node (ref "IR4") (pin "5") (pinfunction "LO_5") (pintype "passive"))
      (node (ref "R57") (pin "2") (pinfunction "2_2") (pintype "passive"))
    )
    (net (code "61") (name "Net-(IR4-VB)") (class "Default")
      (node (ref "C29") (pin "2") (pinfunction "2_2") (pintype "passive"))
      (node (ref "IR4") (pin "8") (pinfunction "VB_8") (pintype "passive"))
      (node (ref "VD4") (pin "2") (pinfunction "K_2") (pintype "passive"))
    )
    (net (code "62") (name "Net-(OLED1-C1N)") (class "Default")
      (node (ref "C18") (pin "1") (pintype "passive"))
      (node (ref "OLED1") (pin "5") (pinfunction "C1N_5") (pintype "passive"))
    )
    (net (code "63") (name "Net-(OLED1-C1P)") (class "Default")
      (node (ref "C18") (pin "2") (pintype "passive"))
      (node (ref "OLED1") (pin "4") (pinfunction "C1P_4") (pintype "passive"))
    )
    (net (code "64") (name "Net-(OLED1-C2N)") (class "Default")
      (node (ref "C17") (pin "1") (pintype "passive"))
      (node (ref "OLED1") (pin "3") (pinfunction "C2N_3") (pintype "passive"))
    )
    (net (code "65") (name "Net-(OLED1-C2P)") (class "Default")
      (node (ref "C17") (pin "2") (pintype "passive"))
      (node (ref "OLED1") (pin "2") (pinfunction "C2P_2") (pintype "passive"))
    )
    (net (code "66") (name "Net-(OLED1-IREF)") (class "Default")
      (node (ref "OLED1") (pin "26") (pinfunction "IREF_26") (pintype "passive"))
      (node (ref "R12") (pin "2") (pintype "passive"))
    )
    (net (code "67") (name "Net-(OLED1-VCC)") (class "Default")
      (node (ref "C21") (pin "2") (pintype "passive"))
      (node (ref "C22") (pin "2") (pintype "passive"))
      (node (ref "OLED1") (pin "28") (pinfunction "VCC_28") (pintype "passive"))
    )
    (net (code "68") (name "Net-(OLED1-VCOMH)") (class "Default")
      (node (ref "C23") (pin "2") (pintype "passive"))
      (node (ref "OLED1") (pin "27") (pinfunction "VCOMH_27") (pintype "passive"))
    )
    (net (code "69") (name "Net-(Q1-G)") (class "Default")
      (node (ref "Q1") (pin "1") (pinfunction "G_1") (pintype "passive"))
      (node (ref "R50") (pin "1") (pinfunction "1_1") (pintype "passive"))
    )
    (net (code "70") (name "Net-(Q2-G)") (class "Default")
      (node (ref "Q2") (pin "1") (pinfunction "G_1") (pintype "passive"))
      (node (ref "R51") (pin "1") (pinfunction "1_1") (pintype "passive"))
    )
    (net (code "71") (name "Net-(Q3-G)") (class "Default")
      (node (ref "Q3") (pin "1") (pinfunction "G_1") (pintype "passive"))
      (node (ref "R52") (pin "1") (pinfunction "1_1") (pintype "passive"))
    )
    (net (code "72") (name "Net-(Q4-G)") (class "Default")
      (node (ref "Q4") (pin "1") (pinfunction "G_1") (pintype "passive"))
      (node (ref "R53") (pin "1") (pinfunction "1_1") (pintype "passive"))
    )
    (net (code "73") (name "Net-(Q5-G)") (class "Default")
      (node (ref "Q5") (pin "1") (pinfunction "G_1") (pintype "passive"))
      (node (ref "R54") (pin "1") (pinfunction "1_1") (pintype "passive"))
    )
    (net (code "74") (name "Net-(Q6-G)") (class "Default")
      (node (ref "Q6") (pin "1") (pinfunction "G_1") (pintype "passive"))
      (node (ref "R55") (pin "1") (pinfunction "1_1") (pintype "passive"))
    )
    (net (code "75") (name "Net-(Q7-G)") (class "Default")
      (node (ref "Q7") (pin "1") (pinfunction "G_1") (pintype "passive"))
      (node (ref "R56") (pin "1") (pinfunction "1_1") (pintype "passive"))
    )
    (net (code "76") (name "Net-(Q8-G)") (class "Default")
      (node (ref "Q8") (pin "1") (pinfunction "G_1") (pintype "passive"))
      (node (ref "R57") (pin "1") (pinfunction "1_1") (pintype "passive"))
    )
    (net (code "77") (name "Net-(U2-BYP)") (class "Default")
      (node (ref "C16") (pin "2") (pintype "passive"))
      (node (ref "U2") (pin "4") (pinfunction "BYP_4") (pintype "passive"))
    )
    (net (code "78") (name "Net-(U5-AD0)") (class "Default")
      (node (ref "R15") (pin "1") (pintype "passive"))
      (node (ref "U5") (pin "9") (pinfunction "AD0_9") (pintype "passive"))
    )
    (net (code "79") (name "Net-(U5-CPOUT)") (class "Default")
      (node (ref "C32") (pin "2") (pintype "passive"))
      (node (ref "U5") (pin "20") (pinfunction "CPOUT_20") (pintype "passive"))
    )
    (net (code "80") (name "Net-(U5-REGOUT)") (class "Default")
      (node (ref "C33") (pin "2") (pintype "passive"))
      (node (ref "U5") (pin "10") (pinfunction "REGOUT_10") (pintype "passive"))
    )
    (net (code "81") (name "Net-(U15-BST)") (class "Default")
      (node (ref "C83") (pin "1") (pintype "passive"))
      (node (ref "U15") (pin "1") (pinfunction "BST_1") (pintype "passive"))
    )
    (net (code "82") (name "Net-(U15-EN)") (class "Default")
      (node (ref "R68") (pin "1") (pintype "passive"))
      (node (ref "U15") (pin "4") (pinfunction "EN_4") (pintype "passive"))
    )
    (net (code "83") (name "Net-(U15-FB)") (class "Default")
      (node (ref "R67") (pin "1") (pintype "passive"))
      (node (ref "R69") (pin "2") (pintype "passive"))
      (node (ref "U15") (pin "3") (pinfunction "FB_3") (pintype "passive"))
    )
    (net (code "84") (name "Net-(U15-IN)") (class "Default")
      (node (ref "C89") (pin "2") (pintype "passive"))
      (node (ref "C90") (pin "2") (pintype "passive"))
      (node (ref "D4") (pin "2") (pintype "passive"))
      (node (ref "R68") (pin "2") (pintype "passive"))
      (node (ref "U15") (pin "5") (pinfunction "IN_5") (pintype "passive"))
    )
    (net (code "85") (name "Net-(U15-SW)") (class "Default")
      (node (ref "C83") (pin "2") (pintype "passive"))
      (node (ref "D3") (pin "2") (pintype "passive"))
      (node (ref "L2") (pin "2") (pinfunction "2_2") (pintype "passive"))
      (node (ref "U15") (pin "6") (pinfunction "SW_6") (pintype "passive"))
    )
    (net (code "86") (name "Net-(USB_TYPEC-D+1(A6))") (class "Default")
      (node (ref "R29") (pin "1") (pintype "passive"))
      (node (ref "R9") (pin "1") (pintype "passive"))
      (node (ref "USB_TYPEC") (pin "6") (pinfunction "D+1(A6)_6") (pintype "passive"))
      (node (ref "USB_TYPEC") (pin "8") (pinfunction "D+2(B6)_8") (pintype "passive"))
    )
    (net (code "87") (name "Net-(USB_TYPEC-D-1(A7))") (class "Default")
      (node (ref "R8") (pin "1") (pintype "passive"))
      (node (ref "USB_TYPEC") (pin "5") (pinfunction "D-2(B7)_5") (pintype "passive"))
      (node (ref "USB_TYPEC") (pin "7") (pinfunction "D-1(A7)_7") (pintype "passive"))
    )
    (net (code "88") (name "POWER") (class "Default")
      (node (ref "C60") (pin "2") (pinfunction "2_2") (pintype "passive"))
      (node (ref "C61") (pin "2") (pinfunction "2_2") (pintype "passive"))
      (node (ref "C62") (pin "2") (pinfunction "2_2") (pintype "passive"))
      (node (ref "C63") (pin "2") (pinfunction "2_2") (pintype "passive"))
      (node (ref "C64") (pin "1") (pinfunction "A_1") (pintype "passive"))
      (node (ref "C65") (pin "1") (pinfunction "1_1") (pintype "passive"))
      (node (ref "IR1") (pin "1") (pinfunction "VCC_1") (pintype "passive"))
      (node (ref "IR2") (pin "1") (pinfunction "VCC_1") (pintype "passive"))
      (node (ref "IR3") (pin "1") (pinfunction "VCC_1") (pintype "passive"))
      (node (ref "IR4") (pin "1") (pinfunction "VCC_1") (pintype "passive"))
      (node (ref "Q1") (pin "2") (pinfunction "D_2") (pintype "passive"))
      (node (ref "Q3") (pin "2") (pinfunction "D_2") (pintype "passive"))
      (node (ref "Q5") (pin "2") (pinfunction "D_2") (pintype "passive"))
      (node (ref "Q7") (pin "2") (pinfunction "D_2") (pintype "passive"))
      (node (ref "VD1") (pin "1") (pinfunction "A_1") (pintype "passive"))
      (node (ref "VD2") (pin "1") (pinfunction "A_1") (pintype "passive"))
      (node (ref "VD3") (pin "1") (pinfunction "A_1") (pintype "passive"))
      (node (ref "VD4") (pin "1") (pinfunction "A_1") (pintype "passive"))
    )
    (net (code "89") (name "VCC3.3") (class "Default")
      (node (ref "C10") (pin "2") (pintype "passive"))
      (node (ref "C12") (pin "2") (pinfunction "2_2") (pintype "passive"))
      (node (ref "C14") (pin "2") (pintype "passive"))
      (node (ref "C15") (pin "2") (pintype "passive"))
      (node (ref "C19") (pin "2") (pintype "passive"))
      (node (ref "C20") (pin "2") (pintype "passive"))
      (node (ref "C31") (pin "2") (pintype "passive"))
      (node (ref "C6") (pin "2") (pintype "passive"))
      (node (ref "C7") (pin "2") (pintype "passive"))
      (node (ref "C8") (pin "2") (pintype "passive"))
      (node (ref "C9") (pin "2") (pintype "passive"))
      (node (ref "DBG") (pin "1") (pinfunction "1_1") (pintype "passive"))
      (node (ref "FPC1") (pin "3") (pinfunction "VCC_3") (pintype "passive"))
      (node (ref "FPC2") (pin "3") (pinfunction "VCC_3") (pintype "passive"))
      (node (ref "OLED1") (pin "6") (pinfunction "VBAT_6") (pintype "passive"))
      (node (ref "OLED1") (pin "9") (pinfunction "VDD_9") (pintype "passive"))
      (node (ref "R13") (pin "2") (pintype "passive"))
      (node (ref "R14") (pin "2") (pintype "passive"))
      (node (ref "R20") (pin "1") (pintype "passive"))
      (node (ref "R29") (pin "2") (pintype "passive"))
      (node (ref "R3") (pin "1") (pintype "passive"))
      (node (ref "U1") (pin "24") (pinfunction "VDD_1_24") (pintype "passive"))
      (node (ref "U1") (pin "36") (pinfunction "VDD_2_36") (pintype "passive"))
      (node (ref "U1") (pin "48") (pinfunction "VDD_3_48") (pintype "passive"))
      (node (ref "U1") (pin "9") (pinfunction "VDDA_9") (pintype "passive"))
      (node (ref "U2") (pin "5") (pinfunction "OUT_5") (pintype "passive"))
      (node (ref "U5") (pin "13") (pinfunction "VDD_13") (pintype "passive"))
      (node (ref "U5") (pin "8") (pinfunction "VLOGIC_8") (pintype "passive"))
    )
    (net (code "90") (name "VCC5") (class "Default")
      (node (ref "C13") (pin "1") (pintype "passive"))
      (node (ref "C84") (pin "2") (pintype "passive"))
      (node (ref "C85") (pin "1") (pinfunction "VCC_1") (pintype "passive"))
      (node (ref "L2") (pin "1") (pinfunction "1_1") (pintype "passive"))
      (node (ref "R69") (pin "1") (pintype "passive"))
      (node (ref "U2") (pin "1") (pinfunction "VIN_1") (pintype "passive"))
      (node (ref "U2") (pin "3") (pinfunction "CE_3") (pintype "passive"))
      (node (ref "USB_TYPEC") (pin "11") (pinfunction "VBUS(B4+A9)_11") (pintype "passive"))
      (node (ref "USB_TYPEC") (pin "2") (pinfunction "VBUS(A4+B9)_2") (pintype "passive"))
    )
    (net (code "91") (name "unconnected-(OLED1-D2-Pad20)") (class "Default")
      (node (ref "OLED1") (pin "20") (pinfunction "D2_20") (pintype "passive"))
    )
    (net (code "92") (name "unconnected-(OLED1-NC(VBREF)-Pad7)") (class "Default")
      (node (ref "OLED1") (pin "7") (pinfunction "NC(VBREF)_7") (pintype "passive"))
    )
    (net (code "93") (name "unconnected-(U5-AUX_CL-Pad7)") (class "Default")
      (node (ref "U5") (pin "7") (pinfunction "AUX_CL_7") (pintype "passive"))
    )
    (net (code "94") (name "unconnected-(U5-AUX_DA-Pad6)") (class "Default")
      (node (ref "U5") (pin "6") (pinfunction "AUX_DA_6") (pintype "passive"))
    )
    (net (code "95") (name "unconnected-(U5-NC-Pad2)") (class "Default")
      (node (ref "U5") (pin "2") (pinfunction "NC_2") (pintype "passive"))
    )
    (net (code "96") (name "unconnected-(U5-NC-Pad3)") (class "Default")
      (node (ref "U5") (pin "3") (pinfunction "NC_3") (pintype "passive"))
    )
    (net (code "97") (name "unconnected-(U5-NC-Pad4)") (class "Default")
      (node (ref "U5") (pin "4") (pinfunction "NC_4") (pintype "passive"))
    )
    (net (code "98") (name "unconnected-(U5-NC-Pad5)") (class "Default")
      (node (ref "U5") (pin "5") (pinfunction "NC_5") (pintype "passive"))
    )
    (net (code "99") (name "unconnected-(U5-NC-Pad14)") (class "Default")
      (node (ref "U5") (pin "14") (pinfunction "NC_14") (pintype "passive"))
    )
    (net (code "100") (name "unconnected-(U5-NC-Pad15)") (class "Default")
      (node (ref "U5") (pin "15") (pinfunction "NC_15") (pintype "passive"))
    )
    (net (code "101") (name "unconnected-(U5-NC-Pad16)") (class "Default")
      (node (ref "U5") (pin "16") (pinfunction "NC_16") (pintype "passive"))
    )
    (net (code "102") (name "unconnected-(U5-NC-Pad17)") (class "Default")
      (node (ref "U5") (pin "17") (pinfunction "NC_17") (pintype "passive"))
    )
    (net (code "103") (name "unconnected-(U5-RESV-Pad19)") (class "Default")
      (node (ref "U5") (pin "19") (pinfunction "RESV_19") (pintype "passive"))
    )
    (net (code "104") (name "unconnected-(U5-RESV-Pad21)") (class "Default")
      (node (ref "U5") (pin "21") (pinfunction "RESV_21") (pintype "passive"))
    )
    (net (code "105") (name "unconnected-(U5-RESV-Pad22)") (class "Default")
      (node (ref "U5") (pin "22") (pinfunction "RESV_22") (pintype "passive"))
    )
    (net (code "106") (name "unconnected-(USB_TYPEC-CC1(A5)-Pad4)") (class "Default")
      (node (ref "USB_TYPEC") (pin "4") (pinfunction "CC1(A5)_4") (pintype "passive"))
    )
    (net (code "107") (name "unconnected-(USB_TYPEC-CC2(B5)-Pad10)") (class "Default")
      (node (ref "USB_TYPEC") (pin "10") (pinfunction "CC2(B5)_10") (pintype "passive"))
    )
    (net (code "108") (name "unconnected-(USB_TYPEC-SBU1(A8)-Pad9)") (class "Default")
      (node (ref "USB_TYPEC") (pin "9") (pinfunction "SBU1(A8)_9") (pintype "passive"))
    )
    (net (code "109") (name "unconnected-(USB_TYPEC-SBU2(B8)-Pad3)") (class "Default")
      (node (ref "USB_TYPEC") (pin "3") (pinfunction "SBU2(B8)_3") (pintype "passive"))
    )
  )
)
